# adc_dac_codec.net
KiCad netlist of a schematic drawn in Altium Designer
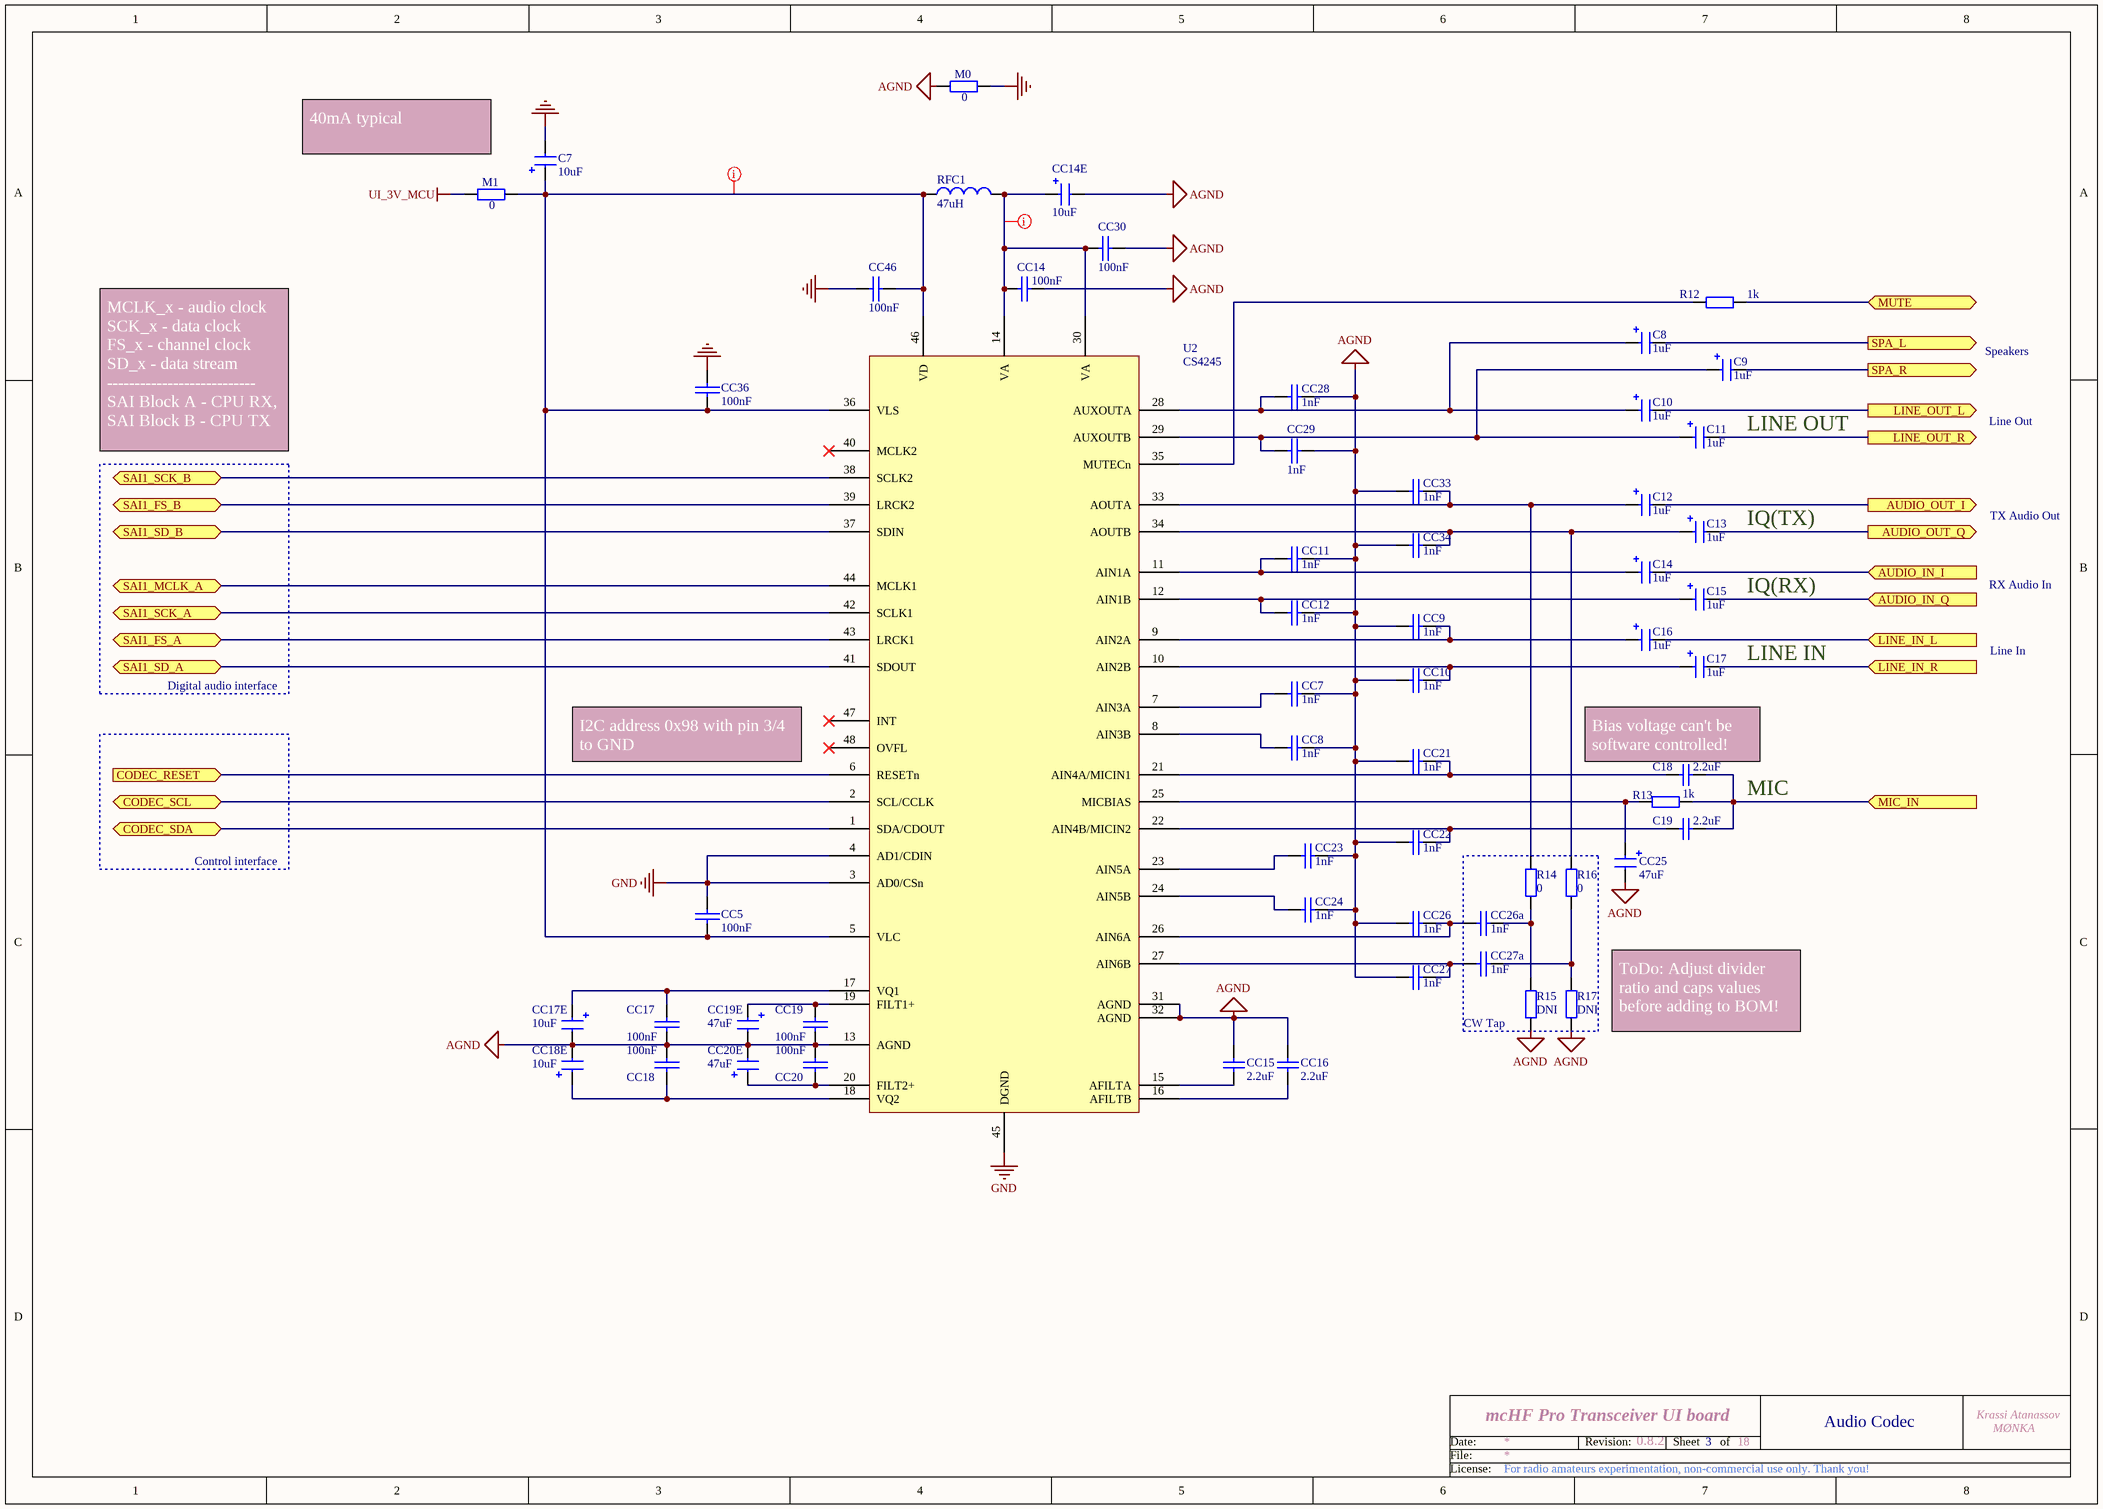
[diagram p0: adc_dac_codec.SchDoc]

(export (version "E")
  (design (tool "Eeschema 10.0.6"))
  (components
    (comp (ref "C7")
      (value "10uF")
      (footprint "1206_Elec_Cap")
      (description "Electrolitic capacitor")
      (libsource (lib "mcHF_ui") (part "CAP-POL"))
    )
    (comp (ref "C8")
      (value "1uF")
      (footprint "1206_Elec_Cap")
      (description "Electrolitic capacitor")
      (libsource (lib "mcHF_ui") (part "CAP-POL"))
    )
    (comp (ref "C9")
      (value "1uF")
      (footprint "1206_Elec_Cap")
      (description "Electrolitic capacitor")
      (libsource (lib "mcHF_ui") (part "CAP-POL"))
    )
    (comp (ref "C10")
      (value "1uF")
      (footprint "1206_Elec_Cap")
      (description "Electrolitic capacitor")
      (libsource (lib "mcHF_ui") (part "CAP-POL"))
    )
    (comp (ref "C11")
      (value "1uF")
      (footprint "1206_Elec_Cap")
      (description "Electrolitic capacitor")
      (libsource (lib "mcHF_ui") (part "CAP-POL"))
    )
    (comp (ref "C12")
      (value "1uF")
      (footprint "1206_Elec_Cap")
      (description "Electrolitic capacitor")
      (libsource (lib "mcHF_ui") (part "CAP-POL"))
    )
    (comp (ref "C13")
      (value "1uF")
      (footprint "1206_Elec_Cap")
      (description "Electrolitic capacitor")
      (libsource (lib "mcHF_ui") (part "CAP-POL"))
    )
    (comp (ref "C14")
      (value "1uF")
      (footprint "1206_Elec_Cap")
      (description "Electrolitic capacitor")
      (libsource (lib "mcHF_ui") (part "CAP-POL"))
    )
    (comp (ref "C15")
      (value "1uF")
      (footprint "1206_Elec_Cap")
      (description "Electrolitic capacitor")
      (libsource (lib "mcHF_ui") (part "CAP-POL"))
    )
    (comp (ref "C16")
      (value "1uF")
      (footprint "1206_Elec_Cap")
      (description "Electrolitic capacitor")
      (libsource (lib "mcHF_ui") (part "CAP-POL"))
    )
    (comp (ref "C17")
      (value "1uF")
      (footprint "1206_Elec_Cap")
      (description "Electrolitic capacitor")
      (libsource (lib "mcHF_ui") (part "CAP-POL"))
    )
    (comp (ref "C18")
      (value "2.2uF")
      (footprint "0805")
      (description "Capacitor")
      (fields (field (name "PUBLISHER") "Altium Limited"))
      (libsource (lib "Miscellaneous Devices") (part "CAP"))
    )
    (comp (ref "C19")
      (value "2.2uF")
      (footprint "0805")
      (description "Capacitor")
      (fields (field (name "PUBLISHER") "Altium Limited"))
      (libsource (lib "Miscellaneous Devices") (part "CAP"))
    )
    (comp (ref "CC5")
      (value "100nF")
      (footprint "0805")
      (description "Capacitor")
      (libsource (lib "mcHF_ui") (part "CAP"))
    )
    (comp (ref "CC7")
      (value "1nF")
      (footprint "0805")
      (description "Capacitor")
      (libsource (lib "mcHF_ui") (part "CAP"))
    )
    (comp (ref "CC8")
      (value "1nF")
      (footprint "0805")
      (description "Capacitor")
      (libsource (lib "mcHF_ui") (part "CAP"))
    )
    (comp (ref "CC9")
      (value "1nF")
      (footprint "0805")
      (description "Capacitor")
      (libsource (lib "mcHF_ui") (part "CAP"))
    )
    (comp (ref "CC10")
      (value "1nF")
      (footprint "0805")
      (description "Capacitor")
      (libsource (lib "mcHF_ui") (part "CAP"))
    )
    (comp (ref "CC11")
      (value "1nF")
      (footprint "0805")
      (description "Capacitor")
      (libsource (lib "mcHF_ui") (part "CAP"))
    )
    (comp (ref "CC12")
      (value "1nF")
      (footprint "0805")
      (description "Capacitor")
      (libsource (lib "mcHF_ui") (part "CAP"))
    )
    (comp (ref "CC14")
      (value "100nF")
      (footprint "0805")
      (description "Capacitor")
      (libsource (lib "mcHF_ui") (part "CAP"))
    )
    (comp (ref "CC14E")
      (value "10uF")
      (footprint "1206_Elec_Cap")
      (description "Electrolitic capacitor")
      (libsource (lib "mcHF_ui") (part "CAP-POL"))
    )
    (comp (ref "CC15")
      (value "2.2uF")
      (footprint "0805")
      (description "Capacitor")
      (fields (field (name "PUBLISHER") "Altium Limited"))
      (libsource (lib "Miscellaneous Devices") (part "CAP"))
    )
    (comp (ref "CC16")
      (value "2.2uF")
      (footprint "0805")
      (description "Capacitor")
      (fields (field (name "PUBLISHER") "Altium Limited"))
      (libsource (lib "Miscellaneous Devices") (part "CAP"))
    )
    (comp (ref "CC17")
      (value "100nF")
      (footprint "0805")
      (description "Capacitor")
      (libsource (lib "mcHF_ui") (part "CAP"))
    )
    (comp (ref "CC17E")
      (value "10uF")
      (footprint "1206_Elec_Cap")
      (description "Electrolitic capacitor")
      (libsource (lib "mcHF_ui") (part "CAP-POL"))
    )
    (comp (ref "CC18")
      (value "100nF")
      (footprint "0805")
      (description "Capacitor")
      (libsource (lib "mcHF_ui") (part "CAP"))
    )
    (comp (ref "CC18E")
      (value "10uF")
      (footprint "1206_Elec_Cap")
      (description "Electrolitic capacitor")
      (libsource (lib "mcHF_ui") (part "CAP-POL"))
    )
    (comp (ref "CC19")
      (value "100nF")
      (footprint "0805")
      (description "Capacitor")
      (libsource (lib "mcHF_ui") (part "CAP"))
    )
    (comp (ref "CC19E")
      (value "47uF")
      (footprint "1206_Elec_Cap")
      (description "Electrolitic capacitor")
      (libsource (lib "mcHF_ui") (part "CAP-POL"))
    )
    (comp (ref "CC20")
      (value "100nF")
      (footprint "0805")
      (description "Capacitor")
      (libsource (lib "mcHF_ui") (part "CAP"))
    )
    (comp (ref "CC20E")
      (value "47uF")
      (footprint "1206_Elec_Cap")
      (description "Electrolitic capacitor")
      (libsource (lib "mcHF_ui") (part "CAP-POL"))
    )
    (comp (ref "CC21")
      (value "1nF")
      (footprint "0805")
      (description "Capacitor")
      (libsource (lib "mcHF_ui") (part "CAP"))
    )
    (comp (ref "CC22")
      (value "1nF")
      (footprint "0805")
      (description "Capacitor")
      (libsource (lib "mcHF_ui") (part "CAP"))
    )
    (comp (ref "CC23")
      (value "1nF")
      (footprint "0805")
      (description "Capacitor")
      (libsource (lib "mcHF_ui") (part "CAP"))
    )
    (comp (ref "CC24")
      (value "1nF")
      (footprint "0805")
      (description "Capacitor")
      (libsource (lib "mcHF_ui") (part "CAP"))
    )
    (comp (ref "CC25")
      (value "47uF")
      (footprint "1206_Elec_Cap")
      (description "Electrolitic capacitor")
      (libsource (lib "mcHF_ui") (part "CAP-POL"))
    )
    (comp (ref "CC26")
      (value "1nF")
      (footprint "0805")
      (description "Capacitor")
      (libsource (lib "mcHF_ui") (part "CAP"))
    )
    (comp (ref "CC26a")
      (value "1nF")
      (footprint "0805")
      (description "Capacitor")
      (libsource (lib "mcHF_ui") (part "CAP"))
    )
    (comp (ref "CC27")
      (value "1nF")
      (footprint "0805")
      (description "Capacitor")
      (libsource (lib "mcHF_ui") (part "CAP"))
    )
    (comp (ref "CC27a")
      (value "1nF")
      (footprint "0805")
      (description "Capacitor")
      (libsource (lib "mcHF_ui") (part "CAP"))
    )
    (comp (ref "CC28")
      (value "1nF")
      (footprint "0805")
      (description "Capacitor")
      (libsource (lib "mcHF_ui") (part "CAP"))
    )
    (comp (ref "CC29")
      (value "1nF")
      (footprint "0805")
      (description "Capacitor")
      (libsource (lib "mcHF_ui") (part "CAP"))
    )
    (comp (ref "CC30")
      (value "100nF")
      (footprint "0805")
      (description "Capacitor")
      (libsource (lib "mcHF_ui") (part "CAP"))
    )
    (comp (ref "CC33")
      (value "1nF")
      (footprint "0805")
      (description "Capacitor")
      (libsource (lib "mcHF_ui") (part "CAP"))
    )
    (comp (ref "CC34")
      (value "1nF")
      (footprint "0805")
      (description "Capacitor")
      (libsource (lib "mcHF_ui") (part "CAP"))
    )
    (comp (ref "CC36")
      (value "100nF")
      (footprint "0805")
      (description "Capacitor")
      (libsource (lib "mcHF_ui") (part "CAP"))
    )
    (comp (ref "CC46")
      (value "100nF")
      (footprint "0805")
      (description "Capacitor")
      (libsource (lib "mcHF_ui") (part "CAP"))
    )
    (comp (ref "M0")
      (value "0")
      (footprint "0805")
      (description "Resistor")
      (libsource (lib "mcHF_rf") (part "RES"))
    )
    (comp (ref "M1")
      (value "0")
      (footprint "0805")
      (description "Resistor")
      (libsource (lib "mcHF_rf") (part "RES"))
    )
    (comp (ref "R12")
      (value "1k")
      (footprint "0805")
      (description "Resistor")
      (libsource (lib "") (part "RES_1"))
    )
    (comp (ref "R13")
      (value "1k")
      (footprint "0805")
      (description "Resistor")
      (libsource (lib "") (part "RES_1"))
    )
    (comp (ref "R14")
      (value "0")
      (footprint "0805")
      (description "Resistor")
      (libsource (lib "mcHF_ui") (part "RES"))
    )
    (comp (ref "R15")
      (value "DNI")
      (footprint "0805")
      (description "Resistor")
      (libsource (lib "mcHF_ui") (part "RES"))
    )
    (comp (ref "R16")
      (value "0")
      (footprint "0805")
      (description "Resistor")
      (libsource (lib "mcHF_ui") (part "RES"))
    )
    (comp (ref "R17")
      (value "DNI")
      (footprint "0805")
      (description "Resistor")
      (libsource (lib "mcHF_ui") (part "RES"))
    )
    (comp (ref "RFC1")
      (value "47uH")
      (footprint "0805")
      (description "Inductor")
      (libsource (lib "mcHF_ui") (part "Inductor"))
    )
    (comp (ref "U2")
      (value "CS4245")
      (footprint "QUAD48")
      (description "Audio CODEC")
      (libsource (lib "__ui") (part "CS4245"))
    )
  )
  (nets
    (net (code "1") (name "/AUDIO_IN_I") (class "Default")
      (node (ref "C14") (pin "2") (pinfunction "2_2") (pintype "passive"))
    )
    (net (code "2") (name "/AUDIO_IN_Q") (class "Default")
      (node (ref "C15") (pin "2") (pinfunction "2_2") (pintype "passive"))
    )
    (net (code "3") (name "/AUDIO_OUT_I") (class "Default")
      (node (ref "C12") (pin "2") (pinfunction "2_2") (pintype "passive"))
    )
    (net (code "4") (name "/AUDIO_OUT_Q") (class "Default")
      (node (ref "C13") (pin "2") (pinfunction "2_2") (pintype "passive"))
    )
    (net (code "5") (name "/CODEC_RESET") (class "Default")
      (node (ref "U2") (pin "6") (pinfunction "RESETn_6") (pintype "passive"))
    )
    (net (code "6") (name "/CODEC_SCL") (class "Default")
      (node (ref "U2") (pin "2") (pinfunction "SCL/CCLK_2") (pintype "passive"))
    )
    (net (code "7") (name "/CODEC_SDA") (class "Default")
      (node (ref "U2") (pin "1") (pinfunction "SDA/CDOUT_1") (pintype "passive"))
    )
    (net (code "8") (name "/LINE_IN_L") (class "Default")
      (node (ref "C16") (pin "2") (pinfunction "2_2") (pintype "passive"))
    )
    (net (code "9") (name "/LINE_IN_R") (class "Default")
      (node (ref "C17") (pin "2") (pinfunction "2_2") (pintype "passive"))
    )
    (net (code "10") (name "/LINE_OUT_L") (class "Default")
      (node (ref "C10") (pin "2") (pinfunction "2_2") (pintype "passive"))
    )
    (net (code "11") (name "/LINE_OUT_R") (class "Default")
      (node (ref "C11") (pin "2") (pinfunction "2_2") (pintype "passive"))
    )
    (net (code "12") (name "/MIC_IN") (class "Default")
      (node (ref "C18") (pin "2") (pinfunction "2_2") (pintype "passive"))
      (node (ref "C19") (pin "2") (pinfunction "2_2") (pintype "passive"))
      (node (ref "R13") (pin "1") (pinfunction "1_1") (pintype "passive"))
    )
    (net (code "13") (name "/MUTE") (class "Default")
      (node (ref "R12") (pin "1") (pinfunction "1_1") (pintype "passive"))
    )
    (net (code "14") (name "/SAI1_FS_A") (class "Default")
      (node (ref "U2") (pin "43") (pinfunction "LRCK1_43") (pintype "passive"))
    )
    (net (code "15") (name "/SAI1_FS_B") (class "Default")
      (node (ref "U2") (pin "39") (pinfunction "LRCK2_39") (pintype "passive"))
    )
    (net (code "16") (name "/SAI1_MCLK_A") (class "Default")
      (node (ref "U2") (pin "44") (pinfunction "MCLK1_44") (pintype "passive"))
    )
    (net (code "17") (name "/SAI1_SCK_A") (class "Default")
      (node (ref "U2") (pin "42") (pinfunction "SCLK1_42") (pintype "passive"))
    )
    (net (code "18") (name "/SAI1_SCK_B") (class "Default")
      (node (ref "U2") (pin "38") (pinfunction "SCLK2_38") (pintype "passive"))
    )
    (net (code "19") (name "/SAI1_SD_A") (class "Default")
      (node (ref "U2") (pin "41") (pinfunction "SDOUT_41") (pintype "passive"))
    )
    (net (code "20") (name "/SAI1_SD_B") (class "Default")
      (node (ref "U2") (pin "37") (pinfunction "SDIN_37") (pintype "passive"))
    )
    (net (code "21") (name "/SPA_L") (class "Default")
      (node (ref "C8") (pin "2") (pinfunction "2_2") (pintype "passive"))
    )
    (net (code "22") (name "/SPA_R") (class "Default")
      (node (ref "C9") (pin "2") (pinfunction "2_2") (pintype "passive"))
    )
    (net (code "23") (name "AGND") (class "Default")
      (node (ref "CC10") (pin "2") (pinfunction "2_2") (pintype "passive"))
      (node (ref "CC11") (pin "1") (pinfunction "1_1") (pintype "passive"))
      (node (ref "CC12") (pin "1") (pinfunction "1_1") (pintype "passive"))
      (node (ref "CC14") (pin "1") (pinfunction "1_1") (pintype "passive"))
      (node (ref "CC14E") (pin "2") (pinfunction "2_2") (pintype "passive"))
      (node (ref "CC15") (pin "1") (pinfunction "1_1") (pintype "passive"))
      (node (ref "CC16") (pin "1") (pinfunction "1_1") (pintype "passive"))
      (node (ref "CC17") (pin "1") (pinfunction "1_1") (pintype "passive"))
      (node (ref "CC17E") (pin "2") (pinfunction "2_2") (pintype "passive"))
      (node (ref "CC18") (pin "2") (pinfunction "2_2") (pintype "passive"))
      (node (ref "CC18E") (pin "2") (pinfunction "2_2") (pintype "passive"))
      (node (ref "CC19") (pin "1") (pinfunction "1_1") (pintype "passive"))
      (node (ref "CC19E") (pin "2") (pinfunction "2_2") (pintype "passive"))
      (node (ref "CC20") (pin "2") (pinfunction "2_2") (pintype "passive"))
      (node (ref "CC20E") (pin "2") (pinfunction "2_2") (pintype "passive"))
      (node (ref "CC21") (pin "2") (pinfunction "2_2") (pintype "passive"))
      (node (ref "CC22") (pin "2") (pinfunction "2_2") (pintype "passive"))
      (node (ref "CC23") (pin "1") (pinfunction "1_1") (pintype "passive"))
      (node (ref "CC24") (pin "1") (pinfunction "1_1") (pintype "passive"))
      (node (ref "CC25") (pin "2") (pinfunction "2_2") (pintype "passive"))
      (node (ref "CC26") (pin "2") (pinfunction "2_2") (pintype "passive"))
      (node (ref "CC27") (pin "2") (pinfunction "2_2") (pintype "passive"))
      (node (ref "CC28") (pin "1") (pinfunction "1_1") (pintype "passive"))
      (node (ref "CC29") (pin "1") (pinfunction "1_1") (pintype "passive"))
      (node (ref "CC30") (pin "1") (pinfunction "1_1") (pintype "passive"))
      (node (ref "CC33") (pin "2") (pinfunction "2_2") (pintype "passive"))
      (node (ref "CC34") (pin "2") (pinfunction "2_2") (pintype "passive"))
      (node (ref "CC7") (pin "1") (pinfunction "1_1") (pintype "passive"))
      (node (ref "CC8") (pin "1") (pinfunction "1_1") (pintype "passive"))
      (node (ref "CC9") (pin "2") (pinfunction "2_2") (pintype "passive"))
      (node (ref "M0") (pin "2") (pinfunction "2_2") (pintype "passive"))
      (node (ref "R15") (pin "2") (pinfunction "2_2") (pintype "passive"))
      (node (ref "R17") (pin "2") (pinfunction "2_2") (pintype "passive"))
      (node (ref "U2") (pin "13") (pinfunction "AGND_13") (pintype "passive"))
      (node (ref "U2") (pin "31") (pinfunction "AGND_31") (pintype "passive"))
      (node (ref "U2") (pin "32") (pinfunction "AGND_32") (pintype "passive"))
    )
    (net (code "24") (name "GND") (class "Default")
      (node (ref "C7") (pin "2") (pinfunction "2_2") (pintype "passive"))
      (node (ref "CC36") (pin "2") (pinfunction "2_2") (pintype "passive"))
      (node (ref "CC46") (pin "2") (pinfunction "2_2") (pintype "passive"))
      (node (ref "CC5") (pin "2") (pinfunction "2_2") (pintype "passive"))
      (node (ref "M0") (pin "1") (pinfunction "1_1") (pintype "passive"))
      (node (ref "U2") (pin "3") (pinfunction "AD0/CSn_3") (pintype "passive"))
      (node (ref "U2") (pin "4") (pinfunction "AD1/CDIN_4") (pintype "passive"))
      (node (ref "U2") (pin "45") (pinfunction "DGND_45") (pintype "passive"))
    )
    (net (code "25") (name "Net-(CC14-Pad2)") (class "Default")
      (node (ref "CC14") (pin "2") (pinfunction "2_2") (pintype "passive"))
      (node (ref "CC14E") (pin "1") (pinfunction "1_1") (pintype "passive"))
      (node (ref "CC30") (pin "2") (pinfunction "2_2") (pintype "passive"))
      (node (ref "RFC1") (pin "2") (pinfunction "2_2") (pintype "passive"))
      (node (ref "U2") (pin "14") (pinfunction "VA_14") (pintype "passive"))
      (node (ref "U2") (pin "30") (pinfunction "VA_30") (pintype "passive"))
    )
    (net (code "26") (name "Net-(CC26a-Pad1)") (class "Default")
      (node (ref "CC26a") (pin "1") (pinfunction "1_1") (pintype "passive"))
      (node (ref "R14") (pin "2") (pinfunction "2_2") (pintype "passive"))
      (node (ref "R15") (pin "1") (pinfunction "1_1") (pintype "passive"))
    )
    (net (code "27") (name "Net-(CC27a-Pad1)") (class "Default")
      (node (ref "CC27a") (pin "1") (pinfunction "1_1") (pintype "passive"))
      (node (ref "R16") (pin "2") (pinfunction "2_2") (pintype "passive"))
      (node (ref "R17") (pin "1") (pinfunction "1_1") (pintype "passive"))
    )
    (net (code "28") (name "Net-(U2-AFILTA)") (class "Default")
      (node (ref "CC15") (pin "2") (pinfunction "2_2") (pintype "passive"))
      (node (ref "U2") (pin "15") (pinfunction "AFILTA_15") (pintype "passive"))
    )
    (net (code "29") (name "Net-(U2-AFILTB)") (class "Default")
      (node (ref "CC16") (pin "2") (pinfunction "2_2") (pintype "passive"))
      (node (ref "U2") (pin "16") (pinfunction "AFILTB_16") (pintype "passive"))
    )
    (net (code "30") (name "Net-(U2-AIN1A)") (class "Default")
      (node (ref "C14") (pin "1") (pinfunction "1_1") (pintype "passive"))
      (node (ref "CC11") (pin "2") (pinfunction "2_2") (pintype "passive"))
      (node (ref "U2") (pin "11") (pinfunction "AIN1A_11") (pintype "passive"))
    )
    (net (code "31") (name "Net-(U2-AIN1B)") (class "Default")
      (node (ref "C15") (pin "1") (pinfunction "1_1") (pintype "passive"))
      (node (ref "CC12") (pin "2") (pinfunction "2_2") (pintype "passive"))
      (node (ref "U2") (pin "12") (pinfunction "AIN1B_12") (pintype "passive"))
    )
    (net (code "32") (name "Net-(U2-AIN2A)") (class "Default")
      (node (ref "C16") (pin "1") (pinfunction "1_1") (pintype "passive"))
      (node (ref "CC9") (pin "1") (pinfunction "1_1") (pintype "passive"))
      (node (ref "U2") (pin "9") (pinfunction "AIN2A_9") (pintype "passive"))
    )
    (net (code "33") (name "Net-(U2-AIN2B)") (class "Default")
      (node (ref "C17") (pin "1") (pinfunction "1_1") (pintype "passive"))
      (node (ref "CC10") (pin "1") (pinfunction "1_1") (pintype "passive"))
      (node (ref "U2") (pin "10") (pinfunction "AIN2B_10") (pintype "passive"))
    )
    (net (code "34") (name "Net-(U2-AIN3A)") (class "Default")
      (node (ref "CC7") (pin "2") (pinfunction "2_2") (pintype "passive"))
      (node (ref "U2") (pin "7") (pinfunction "AIN3A_7") (pintype "passive"))
    )
    (net (code "35") (name "Net-(U2-AIN3B)") (class "Default")
      (node (ref "CC8") (pin "2") (pinfunction "2_2") (pintype "passive"))
      (node (ref "U2") (pin "8") (pinfunction "AIN3B_8") (pintype "passive"))
    )
    (net (code "36") (name "Net-(U2-AIN4A{slash}MICIN1)") (class "Default")
      (node (ref "C18") (pin "1") (pinfunction "1_1") (pintype "passive"))
      (node (ref "CC21") (pin "1") (pinfunction "1_1") (pintype "passive"))
      (node (ref "U2") (pin "21") (pinfunction "AIN4A/MICIN1_21") (pintype "passive"))
    )
    (net (code "37") (name "Net-(U2-AIN4B{slash}MICIN2)") (class "Default")
      (node (ref "C19") (pin "1") (pinfunction "1_1") (pintype "passive"))
      (node (ref "CC22") (pin "1") (pinfunction "1_1") (pintype "passive"))
      (node (ref "U2") (pin "22") (pinfunction "AIN4B/MICIN2_22") (pintype "passive"))
    )
    (net (code "38") (name "Net-(U2-AIN5A)") (class "Default")
      (node (ref "CC23") (pin "2") (pinfunction "2_2") (pintype "passive"))
      (node (ref "U2") (pin "23") (pinfunction "AIN5A_23") (pintype "passive"))
    )
    (net (code "39") (name "Net-(U2-AIN5B)") (class "Default")
      (node (ref "CC24") (pin "2") (pinfunction "2_2") (pintype "passive"))
      (node (ref "U2") (pin "24") (pinfunction "AIN5B_24") (pintype "passive"))
    )
    (net (code "40") (name "Net-(U2-AIN6A)") (class "Default")
      (node (ref "CC26") (pin "1") (pinfunction "1_1") (pintype "passive"))
      (node (ref "CC26a") (pin "2") (pinfunction "2_2") (pintype "passive"))
      (node (ref "U2") (pin "26") (pinfunction "AIN6A_26") (pintype "passive"))
    )
    (net (code "41") (name "Net-(U2-AIN6B)") (class "Default")
      (node (ref "CC27") (pin "1") (pinfunction "1_1") (pintype "passive"))
      (node (ref "CC27a") (pin "2") (pinfunction "2_2") (pintype "passive"))
      (node (ref "U2") (pin "27") (pinfunction "AIN6B_27") (pintype "passive"))
    )
    (net (code "42") (name "Net-(U2-AOUTA)") (class "Default")
      (node (ref "C12") (pin "1") (pinfunction "1_1") (pintype "passive"))
      (node (ref "CC33") (pin "1") (pinfunction "1_1") (pintype "passive"))
      (node (ref "R14") (pin "1") (pinfunction "1_1") (pintype "passive"))
      (node (ref "U2") (pin "33") (pinfunction "AOUTA_33") (pintype "passive"))
    )
    (net (code "43") (name "Net-(U2-AOUTB)") (class "Default")
      (node (ref "C13") (pin "1") (pinfunction "1_1") (pintype "passive"))
      (node (ref "CC34") (pin "1") (pinfunction "1_1") (pintype "passive"))
      (node (ref "R16") (pin "1") (pinfunction "1_1") (pintype "passive"))
      (node (ref "U2") (pin "34") (pinfunction "AOUTB_34") (pintype "passive"))
    )
    (net (code "44") (name "Net-(U2-AUXOUTA)") (class "Default")
      (node (ref "C10") (pin "1") (pinfunction "1_1") (pintype "passive"))
      (node (ref "C8") (pin "1") (pinfunction "1_1") (pintype "passive"))
      (node (ref "CC28") (pin "2") (pinfunction "2_2") (pintype "passive"))
      (node (ref "U2") (pin "28") (pinfunction "AUXOUTA_28") (pintype "passive"))
    )
    (net (code "45") (name "Net-(U2-AUXOUTB)") (class "Default")
      (node (ref "C11") (pin "1") (pinfunction "1_1") (pintype "passive"))
      (node (ref "C9") (pin "1") (pinfunction "1_1") (pintype "passive"))
      (node (ref "CC29") (pin "2") (pinfunction "2_2") (pintype "passive"))
      (node (ref "U2") (pin "29") (pinfunction "AUXOUTB_29") (pintype "passive"))
    )
    (net (code "46") (name "Net-(U2-FILT1+)") (class "Default")
      (node (ref "CC19") (pin "2") (pinfunction "2_2") (pintype "passive"))
      (node (ref "CC19E") (pin "1") (pinfunction "1_1") (pintype "passive"))
      (node (ref "U2") (pin "19") (pinfunction "FILT1+_19") (pintype "passive"))
    )
    (net (code "47") (name "Net-(U2-FILT2+)") (class "Default")
      (node (ref "CC20") (pin "1") (pinfunction "1_1") (pintype "passive"))
      (node (ref "CC20E") (pin "1") (pinfunction "1_1") (pintype "passive"))
      (node (ref "U2") (pin "20") (pinfunction "FILT2+_20") (pintype "passive"))
    )
    (net (code "48") (name "Net-(U2-MICBIAS)") (class "Default")
      (node (ref "CC25") (pin "1") (pinfunction "1_1") (pintype "passive"))
      (node (ref "R13") (pin "2") (pinfunction "2_2") (pintype "passive"))
      (node (ref "U2") (pin "25") (pinfunction "MICBIAS_25") (pintype "passive"))
    )
    (net (code "49") (name "Net-(U2-MUTECn)") (class "Default")
      (node (ref "R12") (pin "2") (pinfunction "2_2") (pintype "passive"))
      (node (ref "U2") (pin "35") (pinfunction "MUTECn_35") (pintype "passive"))
    )
    (net (code "50") (name "Net-(U2-VD)") (class "Default")
      (node (ref "C7") (pin "1") (pinfunction "1_1") (pintype "passive"))
      (node (ref "CC36") (pin "1") (pinfunction "1_1") (pintype "passive"))
      (node (ref "CC46") (pin "1") (pinfunction "1_1") (pintype "passive"))
      (node (ref "CC5") (pin "1") (pinfunction "1_1") (pintype "passive"))
      (node (ref "M1") (pin "1") (pinfunction "1_1") (pintype "passive"))
      (node (ref "RFC1") (pin "1") (pinfunction "1_1") (pintype "passive"))
      (node (ref "U2") (pin "36") (pinfunction "VLS_36") (pintype "passive"))
      (node (ref "U2") (pin "46") (pinfunction "VD_46") (pintype "passive"))
      (node (ref "U2") (pin "5") (pinfunction "VLC_5") (pintype "passive"))
    )
    (net (code "51") (name "Net-(U2-VQ1)") (class "Default")
      (node (ref "CC17") (pin "2") (pinfunction "2_2") (pintype "passive"))
      (node (ref "CC17E") (pin "1") (pinfunction "1_1") (pintype "passive"))
      (node (ref "U2") (pin "17") (pinfunction "VQ1_17") (pintype "passive"))
    )
    (net (code "52") (name "Net-(U2-VQ2)") (class "Default")
      (node (ref "CC18") (pin "1") (pinfunction "1_1") (pintype "passive"))
      (node (ref "CC18E") (pin "1") (pinfunction "1_1") (pintype "passive"))
      (node (ref "U2") (pin "18") (pinfunction "VQ2_18") (pintype "passive"))
    )
    (net (code "53") (name "UI_3V_MCU") (class "Default")
      (node (ref "M1") (pin "2") (pinfunction "2_2") (pintype "passive"))
    )
    (net (code "54") (name "unconnected-(U2-INT-Pad47)") (class "Default")
      (node (ref "U2") (pin "47") (pinfunction "INT_47") (pintype "passive+no_connect"))
    )
    (net (code "55") (name "unconnected-(U2-MCLK2-Pad40)") (class "Default")
      (node (ref "U2") (pin "40") (pinfunction "MCLK2_40") (pintype "passive+no_connect"))
    )
    (net (code "56") (name "unconnected-(U2-OVFL-Pad48)") (class "Default")
      (node (ref "U2") (pin "48") (pinfunction "OVFL_48") (pintype "passive+no_connect"))
    )
  )
)
